# RoboPad.net
KiCad netlist of a schematic drawn in EAGLE
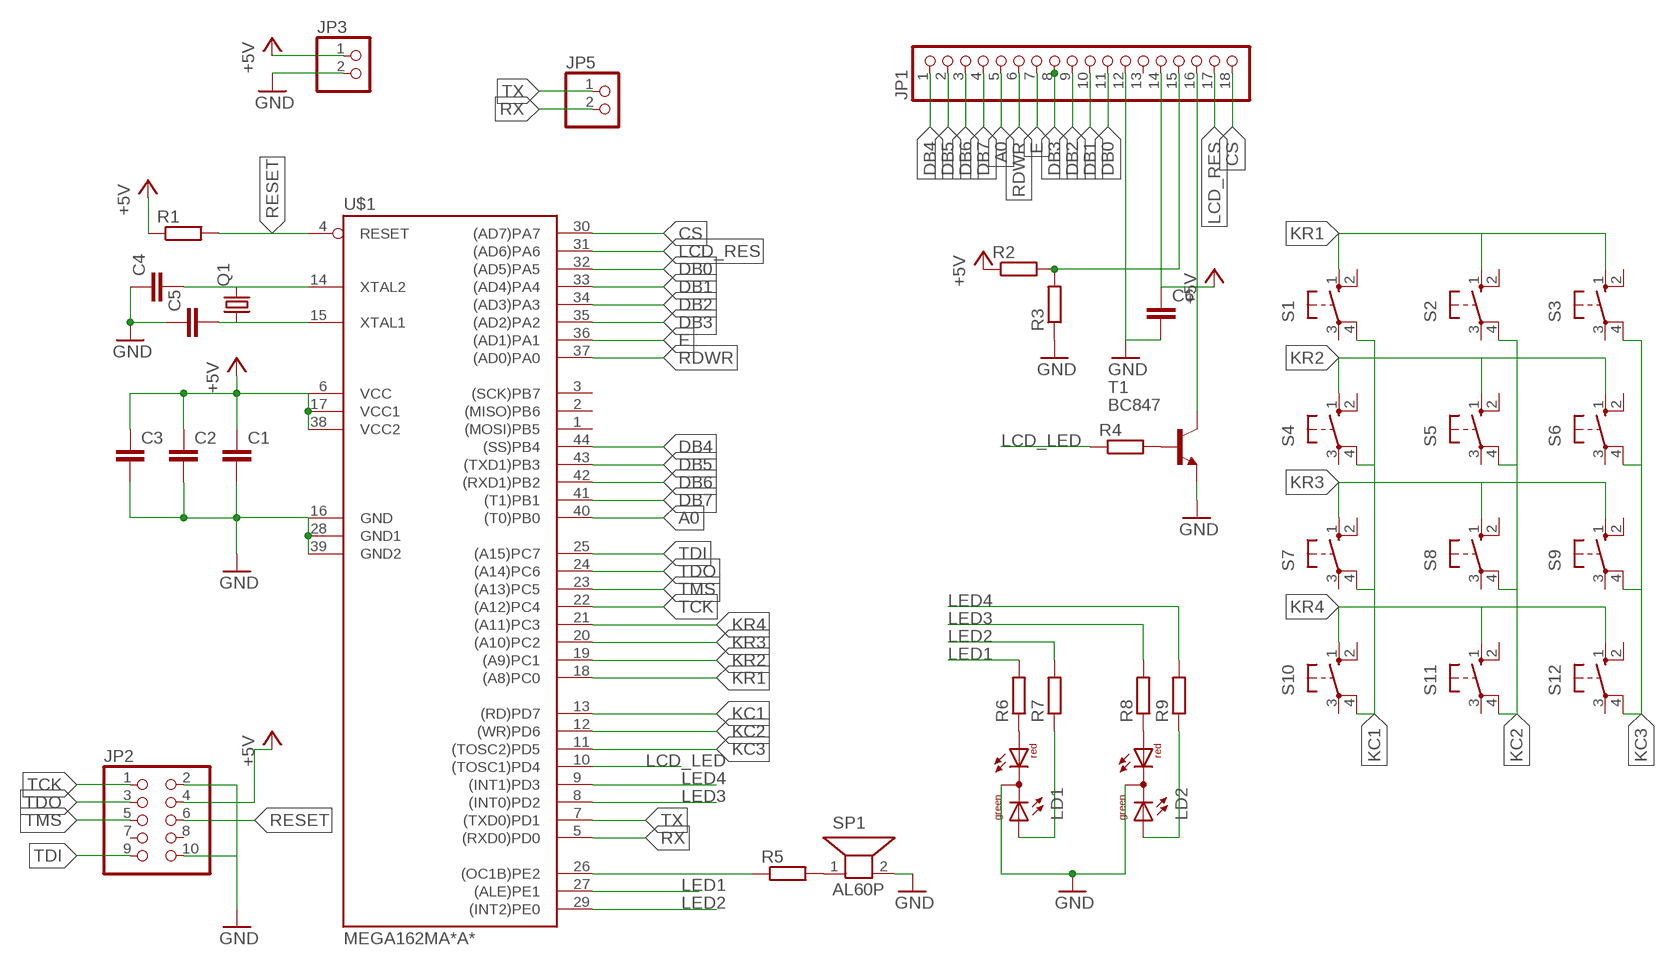
[diagram p0: schematic, sheet 1]

(export (version "E")
  (design (tool "Eeschema 10.0.6"))
  (components
    (comp (ref "C1")
      (value "C-EUC0805")
      (footprint "eagle-import:C0805")
      (libsource (lib "eagle-import") (part "C-EUC0805"))
    )
    (comp (ref "C2")
      (value "C-EUC0805")
      (footprint "eagle-import:C0805")
      (libsource (lib "eagle-import") (part "C-EUC0805"))
    )
    (comp (ref "C3")
      (value "C-EUC0805")
      (footprint "eagle-import:C0805")
      (libsource (lib "eagle-import") (part "C-EUC0805"))
    )
    (comp (ref "C4")
      (value "C-EUC0805")
      (footprint "eagle-import:C0805")
      (libsource (lib "eagle-import") (part "C-EUC0805"))
    )
    (comp (ref "C5")
      (value "C-EUC0805")
      (footprint "eagle-import:C0805")
      (libsource (lib "eagle-import") (part "C-EUC0805"))
    )
    (comp (ref "C6")
      (value "C-EUC0805")
      (footprint "eagle-import:C0805")
      (libsource (lib "eagle-import") (part "C-EUC0805"))
    )
    (comp (ref "JP1")
      (value "PINHD-1X18")
      (footprint "eagle-import:1X18")
      (libsource (lib "eagle-import") (part "PINHD-1X18"))
    )
    (comp (ref "JP2")
      (value "PINHD-2X5")
      (footprint "eagle-import:2X05")
      (libsource (lib "eagle-import") (part "PINHD-2X5"))
    )
    (comp (ref "JP3")
      (value "PINHD-1X2/90")
      (footprint "eagle-import:1X02_90")
      (libsource (lib "eagle-import") (part "PINHD-1X2/90"))
    )
    (comp (ref "JP5")
      (value "PINHD-1X2/90")
      (footprint "eagle-import:1X02_90")
      (libsource (lib "eagle-import") (part "PINHD-1X2/90"))
    )
    (comp (ref "LD1")
      (value "DUOLED-RG-C")
      (footprint "eagle-import:DUOLED-C-5MM")
      (libsource (lib "eagle-import") (part "DUOLED-RG-C"))
    )
    (comp (ref "LD2")
      (value "DUOLED-RG-C")
      (footprint "eagle-import:DUOLED-C-5MM")
      (libsource (lib "eagle-import") (part "DUOLED-RG-C"))
    )
    (comp (ref "Q1")
      (value "CRYSTALHC49U-V")
      (footprint "eagle-import:HC49U-V")
      (libsource (lib "eagle-import") (part "CRYSTALHC49U-V"))
    )
    (comp (ref "R1")
      (value "R-EU_R0805")
      (footprint "eagle-import:R0805")
      (libsource (lib "eagle-import") (part "R-EU_R0805"))
    )
    (comp (ref "R2")
      (value "R-EU_R0805")
      (footprint "eagle-import:R0805")
      (libsource (lib "eagle-import") (part "R-EU_R0805"))
    )
    (comp (ref "R3")
      (value "R-EU_R0805")
      (footprint "eagle-import:R0805")
      (libsource (lib "eagle-import") (part "R-EU_R0805"))
    )
    (comp (ref "R4")
      (value "R-EU_R0805")
      (footprint "eagle-import:R0805")
      (libsource (lib "eagle-import") (part "R-EU_R0805"))
    )
    (comp (ref "R5")
      (value "R-EU_R0805")
      (footprint "eagle-import:R0805")
      (libsource (lib "eagle-import") (part "R-EU_R0805"))
    )
    (comp (ref "R6")
      (value "R-EU_R0805")
      (footprint "eagle-import:R0805")
      (libsource (lib "eagle-import") (part "R-EU_R0805"))
    )
    (comp (ref "R7")
      (value "R-EU_R0805")
      (footprint "eagle-import:R0805")
      (libsource (lib "eagle-import") (part "R-EU_R0805"))
    )
    (comp (ref "R8")
      (value "R-EU_R0805")
      (footprint "eagle-import:R0805")
      (libsource (lib "eagle-import") (part "R-EU_R0805"))
    )
    (comp (ref "R9")
      (value "R-EU_R0805")
      (footprint "eagle-import:R0805")
      (libsource (lib "eagle-import") (part "R-EU_R0805"))
    )
    (comp (ref "S1")
      (value "10-XX")
      (footprint "eagle-import:B3F-10XX")
      (fields (field (name "MPN") "B3F-1000"))
      (libsource (lib "eagle-import") (part "10-XX"))
    )
    (comp (ref "S2")
      (value "10-XX")
      (footprint "eagle-import:B3F-10XX")
      (fields (field (name "MPN") "B3F-1000"))
      (libsource (lib "eagle-import") (part "10-XX"))
    )
    (comp (ref "S3")
      (value "10-XX")
      (footprint "eagle-import:B3F-10XX")
      (fields (field (name "MPN") "B3F-1000"))
      (libsource (lib "eagle-import") (part "10-XX"))
    )
    (comp (ref "S4")
      (value "10-XX")
      (footprint "eagle-import:B3F-10XX")
      (fields (field (name "MPN") "B3F-1000"))
      (libsource (lib "eagle-import") (part "10-XX"))
    )
    (comp (ref "S5")
      (value "10-XX")
      (footprint "eagle-import:B3F-10XX")
      (fields (field (name "MPN") "B3F-1000"))
      (libsource (lib "eagle-import") (part "10-XX"))
    )
    (comp (ref "S6")
      (value "10-XX")
      (footprint "eagle-import:B3F-10XX")
      (fields (field (name "MPN") "B3F-1000"))
      (libsource (lib "eagle-import") (part "10-XX"))
    )
    (comp (ref "S7")
      (value "10-XX")
      (footprint "eagle-import:B3F-10XX")
      (fields (field (name "MPN") "B3F-1000"))
      (libsource (lib "eagle-import") (part "10-XX"))
    )
    (comp (ref "S8")
      (value "10-XX")
      (footprint "eagle-import:B3F-10XX")
      (fields (field (name "MPN") "B3F-1000"))
      (libsource (lib "eagle-import") (part "10-XX"))
    )
    (comp (ref "S9")
      (value "10-XX")
      (footprint "eagle-import:B3F-10XX")
      (fields (field (name "MPN") "B3F-1000"))
      (libsource (lib "eagle-import") (part "10-XX"))
    )
    (comp (ref "S10")
      (value "10-XX")
      (footprint "eagle-import:B3F-10XX")
      (fields (field (name "MPN") "B3F-1000"))
      (libsource (lib "eagle-import") (part "10-XX"))
    )
    (comp (ref "S11")
      (value "10-XX")
      (footprint "eagle-import:B3F-10XX")
      (fields (field (name "MPN") "B3F-1000"))
      (libsource (lib "eagle-import") (part "10-XX"))
    )
    (comp (ref "S12")
      (value "10-XX")
      (footprint "eagle-import:B3F-10XX")
      (fields (field (name "MPN") "B3F-1000"))
      (libsource (lib "eagle-import") (part "10-XX"))
    )
    (comp (ref "SP1")
      (value "AL60P")
      (footprint "eagle-import:AL60P")
      (libsource (lib "eagle-import") (part "AL60P"))
    )
    (comp (ref "T1")
      (value "BC847")
      (footprint "eagle-import:SOT23")
      (libsource (lib "eagle-import") (part "BC847"))
    )
    (comp (ref "U$1")
      (value "MEGA162MA*A*")
      (footprint "eagle-import:TQFP44")
      (libsource (lib "eagle-import") (part "MEGA162MAA"))
    )
  )
  (nets
    (net (code "1") (name "+5V") (class "Default")
      (node (ref "C1") (pin "1") (pinfunction "1_1") (pintype "passive"))
      (node (ref "C2") (pin "1") (pinfunction "1_1") (pintype "passive"))
      (node (ref "C3") (pin "1") (pinfunction "1_1") (pintype "passive"))
      (node (ref "C6") (pin "1") (pinfunction "1_1") (pintype "passive"))
      (node (ref "JP1") (pin "14") (pinfunction "14_14") (pintype "passive"))
      (node (ref "JP2") (pin "4") (pinfunction "4_4") (pintype "passive"))
      (node (ref "JP3") (pin "1") (pinfunction "1_1") (pintype "passive"))
      (node (ref "R1") (pin "1") (pinfunction "1_1") (pintype "passive"))
      (node (ref "R2") (pin "1") (pinfunction "1_1") (pintype "passive"))
      (node (ref "U$1") (pin "17") (pinfunction "VCC1_17") (pintype "power_in"))
      (node (ref "U$1") (pin "38") (pinfunction "VCC2_38") (pintype "power_in"))
      (node (ref "U$1") (pin "6") (pinfunction "VCC_6") (pintype "power_in"))
    )
    (net (code "2") (name "/LCD_LED") (class "Default")
      (node (ref "R4") (pin "1") (pinfunction "1_1") (pintype "passive"))
      (node (ref "U$1") (pin "10") (pinfunction "(TOSC1)PD4_10") (pintype "bidirectional"))
    )
    (net (code "3") (name "/LED1") (class "Default")
      (node (ref "R6") (pin "2") (pinfunction "2_2") (pintype "passive"))
      (node (ref "U$1") (pin "27") (pinfunction "(ALE)PE1_27") (pintype "bidirectional"))
    )
    (net (code "4") (name "/LED2") (class "Default")
      (node (ref "R7") (pin "2") (pinfunction "2_2") (pintype "passive"))
      (node (ref "U$1") (pin "29") (pinfunction "(INT2)PE0_29") (pintype "bidirectional"))
    )
    (net (code "5") (name "/LED3") (class "Default")
      (node (ref "R8") (pin "2") (pinfunction "2_2") (pintype "passive"))
      (node (ref "U$1") (pin "8") (pinfunction "(INT0)PD2_8") (pintype "bidirectional"))
    )
    (net (code "6") (name "/LED4") (class "Default")
      (node (ref "R9") (pin "2") (pinfunction "2_2") (pintype "passive"))
      (node (ref "U$1") (pin "9") (pinfunction "(INT1)PD3_9") (pintype "bidirectional"))
    )
    (net (code "7") (name "A0") (class "Default")
      (node (ref "JP1") (pin "5") (pinfunction "5_5") (pintype "passive"))
      (node (ref "U$1") (pin "40") (pinfunction "(T0)PB0_40") (pintype "bidirectional"))
    )
    (net (code "8") (name "CS") (class "Default")
      (node (ref "JP1") (pin "18") (pinfunction "18_18") (pintype "passive"))
      (node (ref "U$1") (pin "30") (pinfunction "(AD7)PA7_30") (pintype "bidirectional"))
    )
    (net (code "9") (name "DB0") (class "Default")
      (node (ref "JP1") (pin "11") (pinfunction "11_11") (pintype "passive"))
      (node (ref "U$1") (pin "32") (pinfunction "(AD5)PA5_32") (pintype "bidirectional"))
    )
    (net (code "10") (name "DB1") (class "Default")
      (node (ref "JP1") (pin "10") (pinfunction "10_10") (pintype "passive"))
      (node (ref "U$1") (pin "33") (pinfunction "(AD4)PA4_33") (pintype "bidirectional"))
    )
    (net (code "11") (name "DB2") (class "Default")
      (node (ref "JP1") (pin "9") (pinfunction "9_9") (pintype "passive"))
      (node (ref "U$1") (pin "34") (pinfunction "(AD3)PA3_34") (pintype "bidirectional"))
    )
    (net (code "12") (name "DB3") (class "Default")
      (node (ref "JP1") (pin "8") (pinfunction "8_8") (pintype "passive"))
      (node (ref "U$1") (pin "35") (pinfunction "(AD2)PA2_35") (pintype "bidirectional"))
    )
    (net (code "13") (name "DB4") (class "Default")
      (node (ref "JP1") (pin "1") (pinfunction "1_1") (pintype "passive"))
      (node (ref "U$1") (pin "44") (pinfunction "(SS)PB4_44") (pintype "bidirectional"))
    )
    (net (code "14") (name "DB5") (class "Default")
      (node (ref "JP1") (pin "2") (pinfunction "2_2") (pintype "passive"))
      (node (ref "U$1") (pin "43") (pinfunction "(TXD1)PB3_43") (pintype "bidirectional"))
    )
    (net (code "15") (name "DB6") (class "Default")
      (node (ref "JP1") (pin "3") (pinfunction "3_3") (pintype "passive"))
      (node (ref "U$1") (pin "42") (pinfunction "(RXD1)PB2_42") (pintype "bidirectional"))
    )
    (net (code "16") (name "DB7") (class "Default")
      (node (ref "JP1") (pin "4") (pinfunction "4_4") (pintype "passive"))
      (node (ref "U$1") (pin "41") (pinfunction "(T1)PB1_41") (pintype "bidirectional"))
    )
    (net (code "17") (name "E") (class "Default")
      (node (ref "JP1") (pin "7") (pinfunction "7_7") (pintype "passive"))
      (node (ref "U$1") (pin "36") (pinfunction "(AD1)PA1_36") (pintype "bidirectional"))
    )
    (net (code "18") (name "GND") (class "Default")
      (node (ref "C1") (pin "2") (pinfunction "2_2") (pintype "passive"))
      (node (ref "C2") (pin "2") (pinfunction "2_2") (pintype "passive"))
      (node (ref "C3") (pin "2") (pinfunction "2_2") (pintype "passive"))
      (node (ref "C4") (pin "1") (pinfunction "1_1") (pintype "passive"))
      (node (ref "C5") (pin "1") (pinfunction "1_1") (pintype "passive"))
      (node (ref "C6") (pin "2") (pinfunction "2_2") (pintype "passive"))
      (node (ref "JP1") (pin "12") (pinfunction "12_12") (pintype "passive"))
      (node (ref "JP2") (pin "10") (pinfunction "10_10") (pintype "passive"))
      (node (ref "JP2") (pin "2") (pinfunction "2_2") (pintype "passive"))
      (node (ref "JP3") (pin "2") (pinfunction "2_2") (pintype "passive"))
      (node (ref "LD1") (pin "C") (pinfunction "C_C") (pintype "passive"))
      (node (ref "LD2") (pin "C") (pinfunction "C_C") (pintype "passive"))
      (node (ref "R3") (pin "1") (pinfunction "1_1") (pintype "passive"))
      (node (ref "SP1") (pin "2") (pinfunction "2_2") (pintype "passive"))
      (node (ref "T1") (pin "2") (pinfunction "E_2") (pintype "passive"))
      (node (ref "U$1") (pin "16") (pinfunction "GND_16") (pintype "power_in"))
      (node (ref "U$1") (pin "28") (pinfunction "GND1_28") (pintype "power_in"))
      (node (ref "U$1") (pin "39") (pinfunction "GND2_39") (pintype "power_in"))
    )
    (net (code "19") (name "KC1") (class "Default")
      (node (ref "S1") (pin "4") (pinfunction "P1_4") (pintype "passive"))
      (node (ref "S10") (pin "4") (pinfunction "P1_4") (pintype "passive"))
      (node (ref "S4") (pin "4") (pinfunction "P1_4") (pintype "passive"))
      (node (ref "S7") (pin "4") (pinfunction "P1_4") (pintype "passive"))
      (node (ref "U$1") (pin "13") (pinfunction "(RD)PD7_13") (pintype "bidirectional"))
    )
    (net (code "20") (name "KC2") (class "Default")
      (node (ref "S11") (pin "4") (pinfunction "P1_4") (pintype "passive"))
      (node (ref "S2") (pin "4") (pinfunction "P1_4") (pintype "passive"))
      (node (ref "S5") (pin "4") (pinfunction "P1_4") (pintype "passive"))
      (node (ref "S8") (pin "4") (pinfunction "P1_4") (pintype "passive"))
      (node (ref "U$1") (pin "12") (pinfunction "(WR)PD6_12") (pintype "bidirectional"))
    )
    (net (code "21") (name "KC3") (class "Default")
      (node (ref "S12") (pin "4") (pinfunction "P1_4") (pintype "passive"))
      (node (ref "S3") (pin "4") (pinfunction "P1_4") (pintype "passive"))
      (node (ref "S6") (pin "4") (pinfunction "P1_4") (pintype "passive"))
      (node (ref "S9") (pin "4") (pinfunction "P1_4") (pintype "passive"))
      (node (ref "U$1") (pin "11") (pinfunction "(TOSC2)PD5_11") (pintype "bidirectional"))
    )
    (net (code "22") (name "KR1") (class "Default")
      (node (ref "S1") (pin "1") (pinfunction "S_1") (pintype "passive"))
      (node (ref "S2") (pin "1") (pinfunction "S_1") (pintype "passive"))
      (node (ref "S3") (pin "1") (pinfunction "S_1") (pintype "passive"))
      (node (ref "U$1") (pin "18") (pinfunction "(A8)PC0_18") (pintype "bidirectional"))
    )
    (net (code "23") (name "KR2") (class "Default")
      (node (ref "S4") (pin "1") (pinfunction "S_1") (pintype "passive"))
      (node (ref "S5") (pin "1") (pinfunction "S_1") (pintype "passive"))
      (node (ref "S6") (pin "1") (pinfunction "S_1") (pintype "passive"))
      (node (ref "U$1") (pin "19") (pinfunction "(A9)PC1_19") (pintype "bidirectional"))
    )
    (net (code "24") (name "KR3") (class "Default")
      (node (ref "S7") (pin "1") (pinfunction "S_1") (pintype "passive"))
      (node (ref "S8") (pin "1") (pinfunction "S_1") (pintype "passive"))
      (node (ref "S9") (pin "1") (pinfunction "S_1") (pintype "passive"))
      (node (ref "U$1") (pin "20") (pinfunction "(A10)PC2_20") (pintype "bidirectional"))
    )
    (net (code "25") (name "KR4") (class "Default")
      (node (ref "S10") (pin "1") (pinfunction "S_1") (pintype "passive"))
      (node (ref "S11") (pin "1") (pinfunction "S_1") (pintype "passive"))
      (node (ref "S12") (pin "1") (pinfunction "S_1") (pintype "passive"))
      (node (ref "U$1") (pin "21") (pinfunction "(A11)PC3_21") (pintype "bidirectional"))
    )
    (net (code "26") (name "LCD_RES") (class "Default")
      (node (ref "JP1") (pin "17") (pinfunction "17_17") (pintype "passive"))
      (node (ref "U$1") (pin "31") (pinfunction "(AD6)PA6_31") (pintype "bidirectional"))
    )
    (net (code "27") (name "Net-(JP1-Pad15)") (class "Default")
      (node (ref "JP1") (pin "15") (pinfunction "15_15") (pintype "passive"))
      (node (ref "R2") (pin "2") (pinfunction "2_2") (pintype "passive"))
      (node (ref "R3") (pin "2") (pinfunction "2_2") (pintype "passive"))
    )
    (net (code "28") (name "Net-(LD1-AG)") (class "Default")
      (node (ref "LD1") (pin "AX") (pinfunction "AG_AX") (pintype "passive"))
      (node (ref "R7") (pin "1") (pinfunction "1_1") (pintype "passive"))
    )
    (net (code "29") (name "Net-(LD1-PadAR)") (class "Default")
      (node (ref "LD1") (pin "AR") (pinfunction "AR_AR") (pintype "passive"))
      (node (ref "R6") (pin "1") (pinfunction "1_1") (pintype "passive"))
    )
    (net (code "30") (name "Net-(LD2-AG)") (class "Default")
      (node (ref "LD2") (pin "AX") (pinfunction "AG_AX") (pintype "passive"))
      (node (ref "R9") (pin "1") (pinfunction "1_1") (pintype "passive"))
    )
    (net (code "31") (name "Net-(LD2-PadAR)") (class "Default")
      (node (ref "LD2") (pin "AR") (pinfunction "AR_AR") (pintype "passive"))
      (node (ref "R8") (pin "1") (pinfunction "1_1") (pintype "passive"))
    )
    (net (code "32") (name "Net-(R5-Pad2)") (class "Default")
      (node (ref "R5") (pin "2") (pinfunction "2_2") (pintype "passive"))
      (node (ref "SP1") (pin "1") (pinfunction "1_1") (pintype "passive"))
    )
    (net (code "33") (name "Net-(T1-B)") (class "Default")
      (node (ref "R4") (pin "2") (pinfunction "2_2") (pintype "passive"))
      (node (ref "T1") (pin "1") (pinfunction "B_1") (pintype "passive"))
    )
    (net (code "34") (name "Net-(T1-C)") (class "Default")
      (node (ref "JP1") (pin "16") (pinfunction "16_16") (pintype "passive"))
      (node (ref "T1") (pin "3") (pinfunction "C_3") (pintype "passive"))
    )
    (net (code "35") (name "Net-(U$1-(OC1B)PE2)") (class "Default")
      (node (ref "R5") (pin "1") (pinfunction "1_1") (pintype "passive"))
      (node (ref "U$1") (pin "26") (pinfunction "(OC1B)PE2_26") (pintype "bidirectional"))
    )
    (net (code "36") (name "Net-(U$1-XTAL1)") (class "Default")
      (node (ref "C5") (pin "2") (pinfunction "2_2") (pintype "passive"))
      (node (ref "Q1") (pin "1") (pinfunction "1_1") (pintype "passive"))
      (node (ref "U$1") (pin "15") (pinfunction "XTAL1_15") (pintype "input"))
    )
    (net (code "37") (name "Net-(U$1-XTAL2)") (class "Default")
      (node (ref "C4") (pin "2") (pinfunction "2_2") (pintype "passive"))
      (node (ref "Q1") (pin "2") (pinfunction "2_2") (pintype "passive"))
      (node (ref "U$1") (pin "14") (pinfunction "XTAL2_14") (pintype "input"))
    )
    (net (code "38") (name "RDWR") (class "Default")
      (node (ref "JP1") (pin "6") (pinfunction "6_6") (pintype "passive"))
      (node (ref "U$1") (pin "37") (pinfunction "(AD0)PA0_37") (pintype "bidirectional"))
    )
    (net (code "39") (name "RESET") (class "Default")
      (node (ref "JP2") (pin "6") (pinfunction "6_6") (pintype "passive"))
      (node (ref "R1") (pin "2") (pinfunction "2_2") (pintype "passive"))
      (node (ref "U$1") (pin "4") (pinfunction "RESET_4") (pintype "input"))
    )
    (net (code "40") (name "RX") (class "Default")
      (node (ref "JP5") (pin "2") (pinfunction "2_2") (pintype "passive"))
      (node (ref "U$1") (pin "5") (pinfunction "(RXD0)PD0_5") (pintype "bidirectional"))
    )
    (net (code "41") (name "TCK") (class "Default")
      (node (ref "JP2") (pin "1") (pinfunction "1_1") (pintype "passive"))
      (node (ref "U$1") (pin "22") (pinfunction "(A12)PC4_22") (pintype "bidirectional"))
    )
    (net (code "42") (name "TDI") (class "Default")
      (node (ref "JP2") (pin "9") (pinfunction "9_9") (pintype "passive"))
      (node (ref "U$1") (pin "25") (pinfunction "(A15)PC7_25") (pintype "bidirectional"))
    )
    (net (code "43") (name "TDO") (class "Default")
      (node (ref "JP2") (pin "3") (pinfunction "3_3") (pintype "passive"))
      (node (ref "U$1") (pin "24") (pinfunction "(A14)PC6_24") (pintype "bidirectional"))
    )
    (net (code "44") (name "TMS") (class "Default")
      (node (ref "JP2") (pin "5") (pinfunction "5_5") (pintype "passive"))
      (node (ref "U$1") (pin "23") (pinfunction "(A13)PC5_23") (pintype "bidirectional"))
    )
    (net (code "45") (name "TX") (class "Default")
      (node (ref "JP5") (pin "1") (pinfunction "1_1") (pintype "passive"))
      (node (ref "U$1") (pin "7") (pinfunction "(TXD0)PD1_7") (pintype "bidirectional"))
    )
    (net (code "46") (name "unconnected-(JP1-Pad13)") (class "Default")
      (node (ref "JP1") (pin "13") (pinfunction "13_13") (pintype "passive"))
    )
    (net (code "47") (name "unconnected-(JP2-Pad7)") (class "Default")
      (node (ref "JP2") (pin "7") (pinfunction "7_7") (pintype "passive"))
    )
    (net (code "48") (name "unconnected-(JP2-Pad8)") (class "Default")
      (node (ref "JP2") (pin "8") (pinfunction "8_8") (pintype "passive"))
    )
    (net (code "49") (name "unconnected-(S1-P-Pad3)") (class "Default")
      (node (ref "S1") (pin "3") (pinfunction "P_3") (pintype "passive"))
    )
    (net (code "50") (name "unconnected-(S1-S1-Pad2)") (class "Default")
      (node (ref "S1") (pin "2") (pinfunction "S1_2") (pintype "passive"))
    )
    (net (code "51") (name "unconnected-(S2-P-Pad3)") (class "Default")
      (node (ref "S2") (pin "3") (pinfunction "P_3") (pintype "passive"))
    )
    (net (code "52") (name "unconnected-(S2-S1-Pad2)") (class "Default")
      (node (ref "S2") (pin "2") (pinfunction "S1_2") (pintype "passive"))
    )
    (net (code "53") (name "unconnected-(S3-P-Pad3)") (class "Default")
      (node (ref "S3") (pin "3") (pinfunction "P_3") (pintype "passive"))
    )
    (net (code "54") (name "unconnected-(S3-S1-Pad2)") (class "Default")
      (node (ref "S3") (pin "2") (pinfunction "S1_2") (pintype "passive"))
    )
    (net (code "55") (name "unconnected-(S4-P-Pad3)") (class "Default")
      (node (ref "S4") (pin "3") (pinfunction "P_3") (pintype "passive"))
    )
    (net (code "56") (name "unconnected-(S4-S1-Pad2)") (class "Default")
      (node (ref "S4") (pin "2") (pinfunction "S1_2") (pintype "passive"))
    )
    (net (code "57") (name "unconnected-(S5-P-Pad3)") (class "Default")
      (node (ref "S5") (pin "3") (pinfunction "P_3") (pintype "passive"))
    )
    (net (code "58") (name "unconnected-(S5-S1-Pad2)") (class "Default")
      (node (ref "S5") (pin "2") (pinfunction "S1_2") (pintype "passive"))
    )
    (net (code "59") (name "unconnected-(S6-P-Pad3)") (class "Default")
      (node (ref "S6") (pin "3") (pinfunction "P_3") (pintype "passive"))
    )
    (net (code "60") (name "unconnected-(S6-S1-Pad2)") (class "Default")
      (node (ref "S6") (pin "2") (pinfunction "S1_2") (pintype "passive"))
    )
    (net (code "61") (name "unconnected-(S7-P-Pad3)") (class "Default")
      (node (ref "S7") (pin "3") (pinfunction "P_3") (pintype "passive"))
    )
    (net (code "62") (name "unconnected-(S7-S1-Pad2)") (class "Default")
      (node (ref "S7") (pin "2") (pinfunction "S1_2") (pintype "passive"))
    )
    (net (code "63") (name "unconnected-(S8-P-Pad3)") (class "Default")
      (node (ref "S8") (pin "3") (pinfunction "P_3") (pintype "passive"))
    )
    (net (code "64") (name "unconnected-(S8-S1-Pad2)") (class "Default")
      (node (ref "S8") (pin "2") (pinfunction "S1_2") (pintype "passive"))
    )
    (net (code "65") (name "unconnected-(S9-P-Pad3)") (class "Default")
      (node (ref "S9") (pin "3") (pinfunction "P_3") (pintype "passive"))
    )
    (net (code "66") (name "unconnected-(S9-S1-Pad2)") (class "Default")
      (node (ref "S9") (pin "2") (pinfunction "S1_2") (pintype "passive"))
    )
    (net (code "67") (name "unconnected-(S10-P-Pad3)") (class "Default")
      (node (ref "S10") (pin "3") (pinfunction "P_3") (pintype "passive"))
    )
    (net (code "68") (name "unconnected-(S10-S1-Pad2)") (class "Default")
      (node (ref "S10") (pin "2") (pinfunction "S1_2") (pintype "passive"))
    )
    (net (code "69") (name "unconnected-(S11-P-Pad3)") (class "Default")
      (node (ref "S11") (pin "3") (pinfunction "P_3") (pintype "passive"))
    )
    (net (code "70") (name "unconnected-(S11-S1-Pad2)") (class "Default")
      (node (ref "S11") (pin "2") (pinfunction "S1_2") (pintype "passive"))
    )
    (net (code "71") (name "unconnected-(S12-P-Pad3)") (class "Default")
      (node (ref "S12") (pin "3") (pinfunction "P_3") (pintype "passive"))
    )
    (net (code "72") (name "unconnected-(S12-S1-Pad2)") (class "Default")
      (node (ref "S12") (pin "2") (pinfunction "S1_2") (pintype "passive"))
    )
    (net (code "73") (name "unconnected-(U$1-(MISO)PB6-Pad2)") (class "Default")
      (node (ref "U$1") (pin "2") (pinfunction "(MISO)PB6_2") (pintype "bidirectional"))
    )
    (net (code "74") (name "unconnected-(U$1-(MOSI)PB5-Pad1)") (class "Default")
      (node (ref "U$1") (pin "1") (pinfunction "(MOSI)PB5_1") (pintype "bidirectional"))
    )
    (net (code "75") (name "unconnected-(U$1-(SCK)PB7-Pad3)") (class "Default")
      (node (ref "U$1") (pin "3") (pinfunction "(SCK)PB7_3") (pintype "bidirectional"))
    )
  )
)
